# Output_v1_0.net
KiCad netlist of a schematic drawn in EAGLE
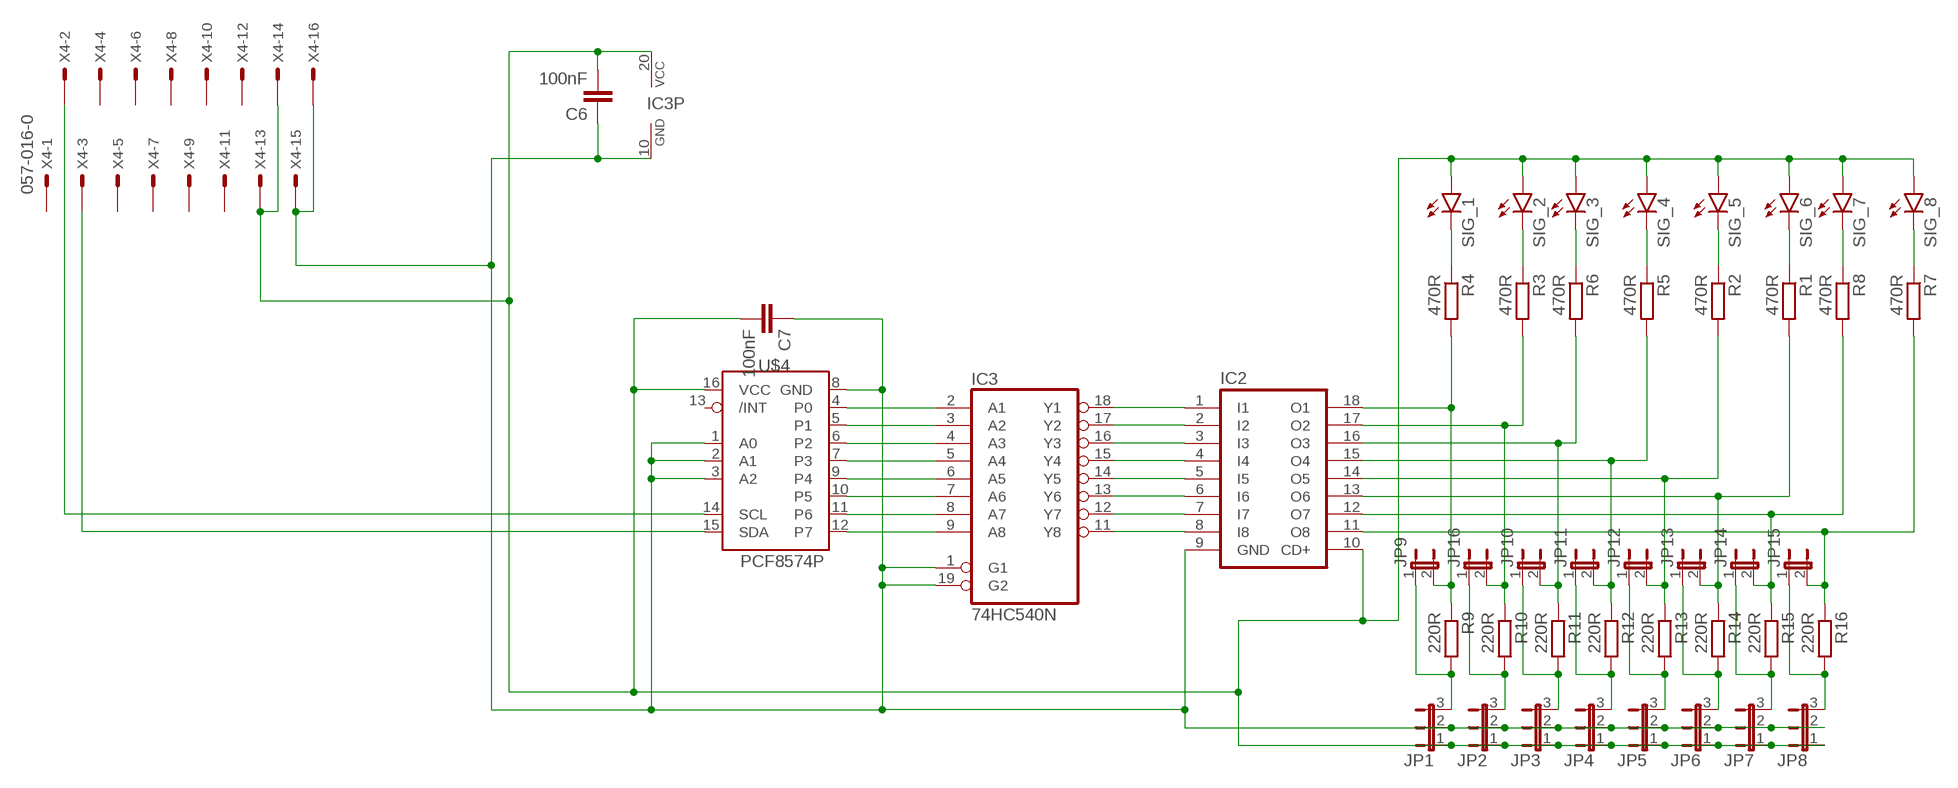
[diagram p0: schematic, sheet 1]

(export (version "E")
  (design (tool "Eeschema 10.0.6"))
  (components
    (comp (ref "C6")
      (value "100nF")
      (footprint "eagle-import:C025-024X044")
      (libsource (lib "eagle-import") (part "C-EU025-024X044"))
    )
    (comp (ref "C7")
      (value "100nF")
      (footprint "eagle-import:C025-024X044")
      (libsource (lib "eagle-import") (part "C-EU025-024X044"))
    )
    (comp (ref "IC2")
      (value "ULN2803A")
      (footprint "eagle-import:DIL18")
      (libsource (lib "eagle-import") (part "ULN2803A"))
    )
    (comp (ref "IC3")
      (value "74HC540N")
      (footprint "eagle-import:DIL20")
      (libsource (lib "eagle-import") (part "74540NHC"))
    )
    (comp (ref "JP1")
      (value "JP2E")
      (footprint "eagle-import:JP2")
      (libsource (lib "eagle-import") (part "JP2E"))
    )
    (comp (ref "JP2")
      (value "JP2E")
      (footprint "eagle-import:JP2")
      (libsource (lib "eagle-import") (part "JP2E"))
    )
    (comp (ref "JP3")
      (value "JP2E")
      (footprint "eagle-import:JP2")
      (libsource (lib "eagle-import") (part "JP2E"))
    )
    (comp (ref "JP4")
      (value "JP2E")
      (footprint "eagle-import:JP2")
      (libsource (lib "eagle-import") (part "JP2E"))
    )
    (comp (ref "JP5")
      (value "JP2E")
      (footprint "eagle-import:JP2")
      (libsource (lib "eagle-import") (part "JP2E"))
    )
    (comp (ref "JP6")
      (value "JP2E")
      (footprint "eagle-import:JP2")
      (libsource (lib "eagle-import") (part "JP2E"))
    )
    (comp (ref "JP7")
      (value "JP2E")
      (footprint "eagle-import:JP2")
      (libsource (lib "eagle-import") (part "JP2E"))
    )
    (comp (ref "JP8")
      (value "JP2E")
      (footprint "eagle-import:JP2")
      (libsource (lib "eagle-import") (part "JP2E"))
    )
    (comp (ref "JP9")
      (value "JP1E")
      (footprint "eagle-import:JP1")
      (libsource (lib "eagle-import") (part "JP1E"))
    )
    (comp (ref "JP10")
      (value "JP1E")
      (footprint "eagle-import:JP1")
      (libsource (lib "eagle-import") (part "JP1E"))
    )
    (comp (ref "JP11")
      (value "JP1E")
      (footprint "eagle-import:JP1")
      (libsource (lib "eagle-import") (part "JP1E"))
    )
    (comp (ref "JP12")
      (value "JP1E")
      (footprint "eagle-import:JP1")
      (libsource (lib "eagle-import") (part "JP1E"))
    )
    (comp (ref "JP13")
      (value "JP1E")
      (footprint "eagle-import:JP1")
      (libsource (lib "eagle-import") (part "JP1E"))
    )
    (comp (ref "JP14")
      (value "JP1E")
      (footprint "eagle-import:JP1")
      (libsource (lib "eagle-import") (part "JP1E"))
    )
    (comp (ref "JP15")
      (value "JP1E")
      (footprint "eagle-import:JP1")
      (libsource (lib "eagle-import") (part "JP1E"))
    )
    (comp (ref "JP16")
      (value "JP1E")
      (footprint "eagle-import:JP1")
      (libsource (lib "eagle-import") (part "JP1E"))
    )
    (comp (ref "R1")
      (value "470R")
      (footprint "eagle-import:0309_10")
      (libsource (lib "eagle-import") (part "R-EU_0309/10"))
    )
    (comp (ref "R2")
      (value "470R")
      (footprint "eagle-import:0309_10")
      (libsource (lib "eagle-import") (part "R-EU_0309/10"))
    )
    (comp (ref "R3")
      (value "470R")
      (footprint "eagle-import:0309_10")
      (libsource (lib "eagle-import") (part "R-EU_0309/10"))
    )
    (comp (ref "R4")
      (value "470R")
      (footprint "eagle-import:0309_10")
      (libsource (lib "eagle-import") (part "R-EU_0309/10"))
    )
    (comp (ref "R5")
      (value "470R")
      (footprint "eagle-import:0309_10")
      (libsource (lib "eagle-import") (part "R-EU_0309/10"))
    )
    (comp (ref "R6")
      (value "470R")
      (footprint "eagle-import:0309_10")
      (libsource (lib "eagle-import") (part "R-EU_0309/10"))
    )
    (comp (ref "R7")
      (value "470R")
      (footprint "eagle-import:0309_10")
      (libsource (lib "eagle-import") (part "R-EU_0309/10"))
    )
    (comp (ref "R8")
      (value "470R")
      (footprint "eagle-import:0309_10")
      (libsource (lib "eagle-import") (part "R-EU_0309/10"))
    )
    (comp (ref "R9")
      (value "220R")
      (footprint "eagle-import:0309_10")
      (libsource (lib "eagle-import") (part "R-EU_0309/10"))
    )
    (comp (ref "R10")
      (value "220R")
      (footprint "eagle-import:0309_10")
      (libsource (lib "eagle-import") (part "R-EU_0309/10"))
    )
    (comp (ref "R11")
      (value "220R")
      (footprint "eagle-import:0309_10")
      (libsource (lib "eagle-import") (part "R-EU_0309/10"))
    )
    (comp (ref "R12")
      (value "220R")
      (footprint "eagle-import:0309_10")
      (libsource (lib "eagle-import") (part "R-EU_0309/10"))
    )
    (comp (ref "R13")
      (value "220R")
      (footprint "eagle-import:0309_10")
      (libsource (lib "eagle-import") (part "R-EU_0309/10"))
    )
    (comp (ref "R14")
      (value "220R")
      (footprint "eagle-import:0309_10")
      (libsource (lib "eagle-import") (part "R-EU_0309/10"))
    )
    (comp (ref "R15")
      (value "220R")
      (footprint "eagle-import:0309_10")
      (libsource (lib "eagle-import") (part "R-EU_0309/10"))
    )
    (comp (ref "R16")
      (value "220R")
      (footprint "eagle-import:0309_10")
      (libsource (lib "eagle-import") (part "R-EU_0309/10"))
    )
    (comp (ref "SIG_1")
      (value "LED3MM")
      (footprint "eagle-import:LED3MM")
      (libsource (lib "eagle-import") (part "LED3MM"))
    )
    (comp (ref "SIG_2")
      (value "LED3MM")
      (footprint "eagle-import:LED3MM")
      (libsource (lib "eagle-import") (part "LED3MM"))
    )
    (comp (ref "SIG_3")
      (value "LED3MM")
      (footprint "eagle-import:LED3MM")
      (libsource (lib "eagle-import") (part "LED3MM"))
    )
    (comp (ref "SIG_4")
      (value "LED3MM")
      (footprint "eagle-import:LED3MM")
      (libsource (lib "eagle-import") (part "LED3MM"))
    )
    (comp (ref "SIG_5")
      (value "LED3MM")
      (footprint "eagle-import:LED3MM")
      (libsource (lib "eagle-import") (part "LED3MM"))
    )
    (comp (ref "SIG_6")
      (value "LED3MM")
      (footprint "eagle-import:LED3MM")
      (libsource (lib "eagle-import") (part "LED3MM"))
    )
    (comp (ref "SIG_7")
      (value "LED3MM")
      (footprint "eagle-import:LED3MM")
      (libsource (lib "eagle-import") (part "LED3MM"))
    )
    (comp (ref "SIG_8")
      (value "LED3MM")
      (footprint "eagle-import:LED3MM")
      (libsource (lib "eagle-import") (part "LED3MM"))
    )
    (comp (ref "U$4")
      (value "PCF8574P")
      (footprint "eagle-import:DIL16")
      (libsource (lib "eagle-import") (part "PCF8574P"))
    )
    (comp (ref "X4")
      (value "057-016-0")
      (footprint "eagle-import:057-016-0")
      (libsource (lib "eagle-import") (part "057-016-0"))
    )
  )
  (nets
    (net (code "1") (name "Net-(IC2-CD+)") (class "Default")
      (node (ref "C6") (pin "2") (pinfunction "2_2") (pintype "passive"))
      (node (ref "C7") (pin "2") (pinfunction "2_2") (pintype "passive"))
      (node (ref "IC2") (pin "10") (pinfunction "CD+_10") (pintype "passive"))
      (node (ref "IC3") (pin "20") (pinfunction "VCC_20") (pintype "power_in"))
      (node (ref "JP1") (pin "1") (pinfunction "1_1") (pintype "passive"))
      (node (ref "JP2") (pin "1") (pinfunction "1_1") (pintype "passive"))
      (node (ref "JP3") (pin "1") (pinfunction "1_1") (pintype "passive"))
      (node (ref "JP4") (pin "1") (pinfunction "1_1") (pintype "passive"))
      (node (ref "JP5") (pin "1") (pinfunction "1_1") (pintype "passive"))
      (node (ref "JP6") (pin "1") (pinfunction "1_1") (pintype "passive"))
      (node (ref "JP7") (pin "1") (pinfunction "1_1") (pintype "passive"))
      (node (ref "JP8") (pin "1") (pinfunction "1_1") (pintype "passive"))
      (node (ref "SIG_1") (pin "A") (pinfunction "A_A") (pintype "passive"))
      (node (ref "SIG_2") (pin "A") (pinfunction "A_A") (pintype "passive"))
      (node (ref "SIG_3") (pin "A") (pinfunction "A_A") (pintype "passive"))
      (node (ref "SIG_4") (pin "A") (pinfunction "A_A") (pintype "passive"))
      (node (ref "SIG_5") (pin "A") (pinfunction "A_A") (pintype "passive"))
      (node (ref "SIG_6") (pin "A") (pinfunction "A_A") (pintype "passive"))
      (node (ref "SIG_7") (pin "A") (pinfunction "A_A") (pintype "passive"))
      (node (ref "SIG_8") (pin "A") (pinfunction "A_A") (pintype "passive"))
      (node (ref "U$4") (pin "16") (pinfunction "VCC_16") (pintype "power_in"))
      (node (ref "X4") (pin "13") (pinfunction "S_13") (pintype "passive"))
      (node (ref "X4") (pin "14") (pinfunction "S_14") (pintype "passive"))
    )
    (net (code "2") (name "Net-(IC2-GND)") (class "Default")
      (node (ref "C6") (pin "1") (pinfunction "1_1") (pintype "passive"))
      (node (ref "C7") (pin "1") (pinfunction "1_1") (pintype "passive"))
      (node (ref "IC2") (pin "9") (pinfunction "GND_9") (pintype "power_in"))
      (node (ref "IC3") (pin "1") (pinfunction "G1_1") (pintype "input"))
      (node (ref "IC3") (pin "10") (pinfunction "GND_10") (pintype "power_in"))
      (node (ref "IC3") (pin "19") (pinfunction "G2_19") (pintype "input"))
      (node (ref "JP1") (pin "2") (pinfunction "2_2") (pintype "passive"))
      (node (ref "JP2") (pin "2") (pinfunction "2_2") (pintype "passive"))
      (node (ref "JP3") (pin "2") (pinfunction "2_2") (pintype "passive"))
      (node (ref "JP4") (pin "2") (pinfunction "2_2") (pintype "passive"))
      (node (ref "JP5") (pin "2") (pinfunction "2_2") (pintype "passive"))
      (node (ref "JP6") (pin "2") (pinfunction "2_2") (pintype "passive"))
      (node (ref "JP7") (pin "2") (pinfunction "2_2") (pintype "passive"))
      (node (ref "JP8") (pin "2") (pinfunction "2_2") (pintype "passive"))
      (node (ref "U$4") (pin "1") (pinfunction "A0_1") (pintype "input"))
      (node (ref "U$4") (pin "2") (pinfunction "A1_2") (pintype "input"))
      (node (ref "U$4") (pin "3") (pinfunction "A2_3") (pintype "input"))
      (node (ref "U$4") (pin "8") (pinfunction "GND_8") (pintype "power_in"))
      (node (ref "X4") (pin "15") (pinfunction "S_15") (pintype "passive"))
      (node (ref "X4") (pin "16") (pinfunction "S_16") (pintype "passive"))
    )
    (net (code "3") (name "Net-(IC2-I1)") (class "Default")
      (node (ref "IC2") (pin "1") (pinfunction "I1_1") (pintype "input"))
      (node (ref "IC3") (pin "18") (pinfunction "Y1_18") (pintype "tri_state"))
    )
    (net (code "4") (name "Net-(IC2-I2)") (class "Default")
      (node (ref "IC2") (pin "2") (pinfunction "I2_2") (pintype "input"))
      (node (ref "IC3") (pin "17") (pinfunction "Y2_17") (pintype "tri_state"))
    )
    (net (code "5") (name "Net-(IC2-I3)") (class "Default")
      (node (ref "IC2") (pin "3") (pinfunction "I3_3") (pintype "input"))
      (node (ref "IC3") (pin "16") (pinfunction "Y3_16") (pintype "tri_state"))
    )
    (net (code "6") (name "Net-(IC2-I4)") (class "Default")
      (node (ref "IC2") (pin "4") (pinfunction "I4_4") (pintype "input"))
      (node (ref "IC3") (pin "15") (pinfunction "Y4_15") (pintype "tri_state"))
    )
    (net (code "7") (name "Net-(IC2-I5)") (class "Default")
      (node (ref "IC2") (pin "5") (pinfunction "I5_5") (pintype "input"))
      (node (ref "IC3") (pin "14") (pinfunction "Y5_14") (pintype "tri_state"))
    )
    (net (code "8") (name "Net-(IC2-I6)") (class "Default")
      (node (ref "IC2") (pin "6") (pinfunction "I6_6") (pintype "input"))
      (node (ref "IC3") (pin "13") (pinfunction "Y6_13") (pintype "tri_state"))
    )
    (net (code "9") (name "Net-(IC2-I7)") (class "Default")
      (node (ref "IC2") (pin "7") (pinfunction "I7_7") (pintype "input"))
      (node (ref "IC3") (pin "12") (pinfunction "Y7_12") (pintype "tri_state"))
    )
    (net (code "10") (name "Net-(IC2-I8)") (class "Default")
      (node (ref "IC2") (pin "8") (pinfunction "I8_8") (pintype "input"))
      (node (ref "IC3") (pin "11") (pinfunction "Y8_11") (pintype "tri_state"))
    )
    (net (code "11") (name "Net-(IC2-O1)") (class "Default")
      (node (ref "IC2") (pin "18") (pinfunction "O1_18") (pintype "open_collector"))
      (node (ref "JP9") (pin "2") (pinfunction "2_2") (pintype "passive"))
      (node (ref "R4") (pin "2") (pinfunction "2_2") (pintype "passive"))
      (node (ref "R9") (pin "1") (pinfunction "1_1") (pintype "passive"))
    )
    (net (code "12") (name "Net-(IC2-O2)") (class "Default")
      (node (ref "IC2") (pin "17") (pinfunction "O2_17") (pintype "open_collector"))
      (node (ref "JP16") (pin "2") (pinfunction "2_2") (pintype "passive"))
      (node (ref "R10") (pin "1") (pinfunction "1_1") (pintype "passive"))
      (node (ref "R3") (pin "2") (pinfunction "2_2") (pintype "passive"))
    )
    (net (code "13") (name "Net-(IC2-O3)") (class "Default")
      (node (ref "IC2") (pin "16") (pinfunction "O3_16") (pintype "open_collector"))
      (node (ref "JP10") (pin "2") (pinfunction "2_2") (pintype "passive"))
      (node (ref "R11") (pin "1") (pinfunction "1_1") (pintype "passive"))
      (node (ref "R6") (pin "2") (pinfunction "2_2") (pintype "passive"))
    )
    (net (code "14") (name "Net-(IC2-O4)") (class "Default")
      (node (ref "IC2") (pin "15") (pinfunction "O4_15") (pintype "open_collector"))
      (node (ref "JP11") (pin "2") (pinfunction "2_2") (pintype "passive"))
      (node (ref "R12") (pin "1") (pinfunction "1_1") (pintype "passive"))
      (node (ref "R5") (pin "2") (pinfunction "2_2") (pintype "passive"))
    )
    (net (code "15") (name "Net-(IC2-O5)") (class "Default")
      (node (ref "IC2") (pin "14") (pinfunction "O5_14") (pintype "open_collector"))
      (node (ref "JP12") (pin "2") (pinfunction "2_2") (pintype "passive"))
      (node (ref "R13") (pin "1") (pinfunction "1_1") (pintype "passive"))
      (node (ref "R2") (pin "2") (pinfunction "2_2") (pintype "passive"))
    )
    (net (code "16") (name "Net-(IC2-O6)") (class "Default")
      (node (ref "IC2") (pin "13") (pinfunction "O6_13") (pintype "open_collector"))
      (node (ref "JP13") (pin "2") (pinfunction "2_2") (pintype "passive"))
      (node (ref "R1") (pin "2") (pinfunction "2_2") (pintype "passive"))
      (node (ref "R14") (pin "1") (pinfunction "1_1") (pintype "passive"))
    )
    (net (code "17") (name "Net-(IC2-O7)") (class "Default")
      (node (ref "IC2") (pin "12") (pinfunction "O7_12") (pintype "open_collector"))
      (node (ref "JP14") (pin "2") (pinfunction "2_2") (pintype "passive"))
      (node (ref "R15") (pin "1") (pinfunction "1_1") (pintype "passive"))
      (node (ref "R8") (pin "2") (pinfunction "2_2") (pintype "passive"))
    )
    (net (code "18") (name "Net-(IC2-O8)") (class "Default")
      (node (ref "IC2") (pin "11") (pinfunction "O8_11") (pintype "open_collector"))
      (node (ref "JP15") (pin "2") (pinfunction "2_2") (pintype "passive"))
      (node (ref "R16") (pin "1") (pinfunction "1_1") (pintype "passive"))
      (node (ref "R7") (pin "2") (pinfunction "2_2") (pintype "passive"))
    )
    (net (code "19") (name "Net-(IC3A-A1)") (class "Default")
      (node (ref "IC3") (pin "2") (pinfunction "A1_2") (pintype "input"))
      (node (ref "U$4") (pin "4") (pinfunction "P0_4") (pintype "bidirectional"))
    )
    (net (code "20") (name "Net-(IC3A-A2)") (class "Default")
      (node (ref "IC3") (pin "3") (pinfunction "A2_3") (pintype "input"))
      (node (ref "U$4") (pin "5") (pinfunction "P1_5") (pintype "bidirectional"))
    )
    (net (code "21") (name "Net-(IC3A-A3)") (class "Default")
      (node (ref "IC3") (pin "4") (pinfunction "A3_4") (pintype "input"))
      (node (ref "U$4") (pin "6") (pinfunction "P2_6") (pintype "bidirectional"))
    )
    (net (code "22") (name "Net-(IC3A-A4)") (class "Default")
      (node (ref "IC3") (pin "5") (pinfunction "A4_5") (pintype "input"))
      (node (ref "U$4") (pin "7") (pinfunction "P3_7") (pintype "bidirectional"))
    )
    (net (code "23") (name "Net-(IC3A-A5)") (class "Default")
      (node (ref "IC3") (pin "6") (pinfunction "A5_6") (pintype "input"))
      (node (ref "U$4") (pin "9") (pinfunction "P4_9") (pintype "bidirectional"))
    )
    (net (code "24") (name "Net-(IC3A-A6)") (class "Default")
      (node (ref "IC3") (pin "7") (pinfunction "A6_7") (pintype "input"))
      (node (ref "U$4") (pin "10") (pinfunction "P5_10") (pintype "bidirectional"))
    )
    (net (code "25") (name "Net-(IC3A-A7)") (class "Default")
      (node (ref "IC3") (pin "8") (pinfunction "A7_8") (pintype "input"))
      (node (ref "U$4") (pin "11") (pinfunction "P6_11") (pintype "bidirectional"))
    )
    (net (code "26") (name "Net-(IC3A-A8)") (class "Default")
      (node (ref "IC3") (pin "9") (pinfunction "A8_9") (pintype "input"))
      (node (ref "U$4") (pin "12") (pinfunction "P7_12") (pintype "bidirectional"))
    )
    (net (code "27") (name "Net-(JP1-Pad3)") (class "Default")
      (node (ref "JP1") (pin "3") (pinfunction "3_3") (pintype "passive"))
      (node (ref "JP9") (pin "1") (pinfunction "1_1") (pintype "passive"))
      (node (ref "R9") (pin "2") (pinfunction "2_2") (pintype "passive"))
    )
    (net (code "28") (name "Net-(JP10-Pad1)") (class "Default")
      (node (ref "JP10") (pin "1") (pinfunction "1_1") (pintype "passive"))
      (node (ref "JP3") (pin "3") (pinfunction "3_3") (pintype "passive"))
      (node (ref "R11") (pin "2") (pinfunction "2_2") (pintype "passive"))
    )
    (net (code "29") (name "Net-(JP11-Pad1)") (class "Default")
      (node (ref "JP11") (pin "1") (pinfunction "1_1") (pintype "passive"))
      (node (ref "JP4") (pin "3") (pinfunction "3_3") (pintype "passive"))
      (node (ref "R12") (pin "2") (pinfunction "2_2") (pintype "passive"))
    )
    (net (code "30") (name "Net-(JP12-Pad1)") (class "Default")
      (node (ref "JP12") (pin "1") (pinfunction "1_1") (pintype "passive"))
      (node (ref "JP5") (pin "3") (pinfunction "3_3") (pintype "passive"))
      (node (ref "R13") (pin "2") (pinfunction "2_2") (pintype "passive"))
    )
    (net (code "31") (name "Net-(JP13-Pad1)") (class "Default")
      (node (ref "JP13") (pin "1") (pinfunction "1_1") (pintype "passive"))
      (node (ref "JP6") (pin "3") (pinfunction "3_3") (pintype "passive"))
      (node (ref "R14") (pin "2") (pinfunction "2_2") (pintype "passive"))
    )
    (net (code "32") (name "Net-(JP14-Pad1)") (class "Default")
      (node (ref "JP14") (pin "1") (pinfunction "1_1") (pintype "passive"))
      (node (ref "JP7") (pin "3") (pinfunction "3_3") (pintype "passive"))
      (node (ref "R15") (pin "2") (pinfunction "2_2") (pintype "passive"))
    )
    (net (code "33") (name "Net-(JP15-Pad1)") (class "Default")
      (node (ref "JP15") (pin "1") (pinfunction "1_1") (pintype "passive"))
      (node (ref "JP8") (pin "3") (pinfunction "3_3") (pintype "passive"))
      (node (ref "R16") (pin "2") (pinfunction "2_2") (pintype "passive"))
    )
    (net (code "34") (name "Net-(JP16-Pad1)") (class "Default")
      (node (ref "JP16") (pin "1") (pinfunction "1_1") (pintype "passive"))
      (node (ref "JP2") (pin "3") (pinfunction "3_3") (pintype "passive"))
      (node (ref "R10") (pin "2") (pinfunction "2_2") (pintype "passive"))
    )
    (net (code "35") (name "Net-(SIG_1-C)") (class "Default")
      (node (ref "R4") (pin "1") (pinfunction "1_1") (pintype "passive"))
      (node (ref "SIG_1") (pin "K") (pinfunction "C_K") (pintype "passive"))
    )
    (net (code "36") (name "Net-(SIG_2-C)") (class "Default")
      (node (ref "R3") (pin "1") (pinfunction "1_1") (pintype "passive"))
      (node (ref "SIG_2") (pin "K") (pinfunction "C_K") (pintype "passive"))
    )
    (net (code "37") (name "Net-(SIG_3-C)") (class "Default")
      (node (ref "R6") (pin "1") (pinfunction "1_1") (pintype "passive"))
      (node (ref "SIG_3") (pin "K") (pinfunction "C_K") (pintype "passive"))
    )
    (net (code "38") (name "Net-(SIG_4-C)") (class "Default")
      (node (ref "R5") (pin "1") (pinfunction "1_1") (pintype "passive"))
      (node (ref "SIG_4") (pin "K") (pinfunction "C_K") (pintype "passive"))
    )
    (net (code "39") (name "Net-(SIG_5-C)") (class "Default")
      (node (ref "R2") (pin "1") (pinfunction "1_1") (pintype "passive"))
      (node (ref "SIG_5") (pin "K") (pinfunction "C_K") (pintype "passive"))
    )
    (net (code "40") (name "Net-(SIG_6-C)") (class "Default")
      (node (ref "R1") (pin "1") (pinfunction "1_1") (pintype "passive"))
      (node (ref "SIG_6") (pin "K") (pinfunction "C_K") (pintype "passive"))
    )
    (net (code "41") (name "Net-(SIG_7-C)") (class "Default")
      (node (ref "R8") (pin "1") (pinfunction "1_1") (pintype "passive"))
      (node (ref "SIG_7") (pin "K") (pinfunction "C_K") (pintype "passive"))
    )
    (net (code "42") (name "Net-(SIG_8-C)") (class "Default")
      (node (ref "R7") (pin "1") (pinfunction "1_1") (pintype "passive"))
      (node (ref "SIG_8") (pin "K") (pinfunction "C_K") (pintype "passive"))
    )
    (net (code "43") (name "Net-(U$4-SCL)") (class "Default")
      (node (ref "U$4") (pin "14") (pinfunction "SCL_14") (pintype "input"))
      (node (ref "X4") (pin "2") (pinfunction "S_2") (pintype "passive"))
    )
    (net (code "44") (name "Net-(U$4-SDA)") (class "Default")
      (node (ref "U$4") (pin "15") (pinfunction "SDA_15") (pintype "bidirectional"))
      (node (ref "X4") (pin "3") (pinfunction "S_3") (pintype "passive"))
    )
    (net (code "45") (name "unconnected-(U$4-{slash}INT-Pad13)") (class "Default")
      (node (ref "U$4") (pin "13") (pinfunction "/INT_13") (pintype "output"))
    )
    (net (code "46") (name "unconnected-(X4A-S-Pad1)") (class "Default")
      (node (ref "X4") (pin "1") (pinfunction "S_1") (pintype "passive"))
    )
    (net (code "47") (name "unconnected-(X4B-S-Pad10)") (class "Default")
      (node (ref "X4") (pin "10") (pinfunction "S_10") (pintype "passive"))
    )
    (net (code "48") (name "unconnected-(X4C-S-Pad11)") (class "Default")
      (node (ref "X4") (pin "11") (pinfunction "S_11") (pintype "passive"))
    )
    (net (code "49") (name "unconnected-(X4D-S-Pad12)") (class "Default")
      (node (ref "X4") (pin "12") (pinfunction "S_12") (pintype "passive"))
    )
    (net (code "50") (name "unconnected-(X4K-S-Pad4)") (class "Default")
      (node (ref "X4") (pin "4") (pinfunction "S_4") (pintype "passive"))
    )
    (net (code "51") (name "unconnected-(X4L-S-Pad5)") (class "Default")
      (node (ref "X4") (pin "5") (pinfunction "S_5") (pintype "passive"))
    )
    (net (code "52") (name "unconnected-(X4M-S-Pad6)") (class "Default")
      (node (ref "X4") (pin "6") (pinfunction "S_6") (pintype "passive"))
    )
    (net (code "53") (name "unconnected-(X4N-S-Pad7)") (class "Default")
      (node (ref "X4") (pin "7") (pinfunction "S_7") (pintype "passive"))
    )
    (net (code "54") (name "unconnected-(X4O-S-Pad8)") (class "Default")
      (node (ref "X4") (pin "8") (pinfunction "S_8") (pintype "passive"))
    )
    (net (code "55") (name "unconnected-(X4P-S-Pad9)") (class "Default")
      (node (ref "X4") (pin "9") (pinfunction "S_9") (pintype "passive"))
    )
  )
)
